# 3ch_mix_1_2.net
KiCad netlist of a schematic drawn in EAGLE
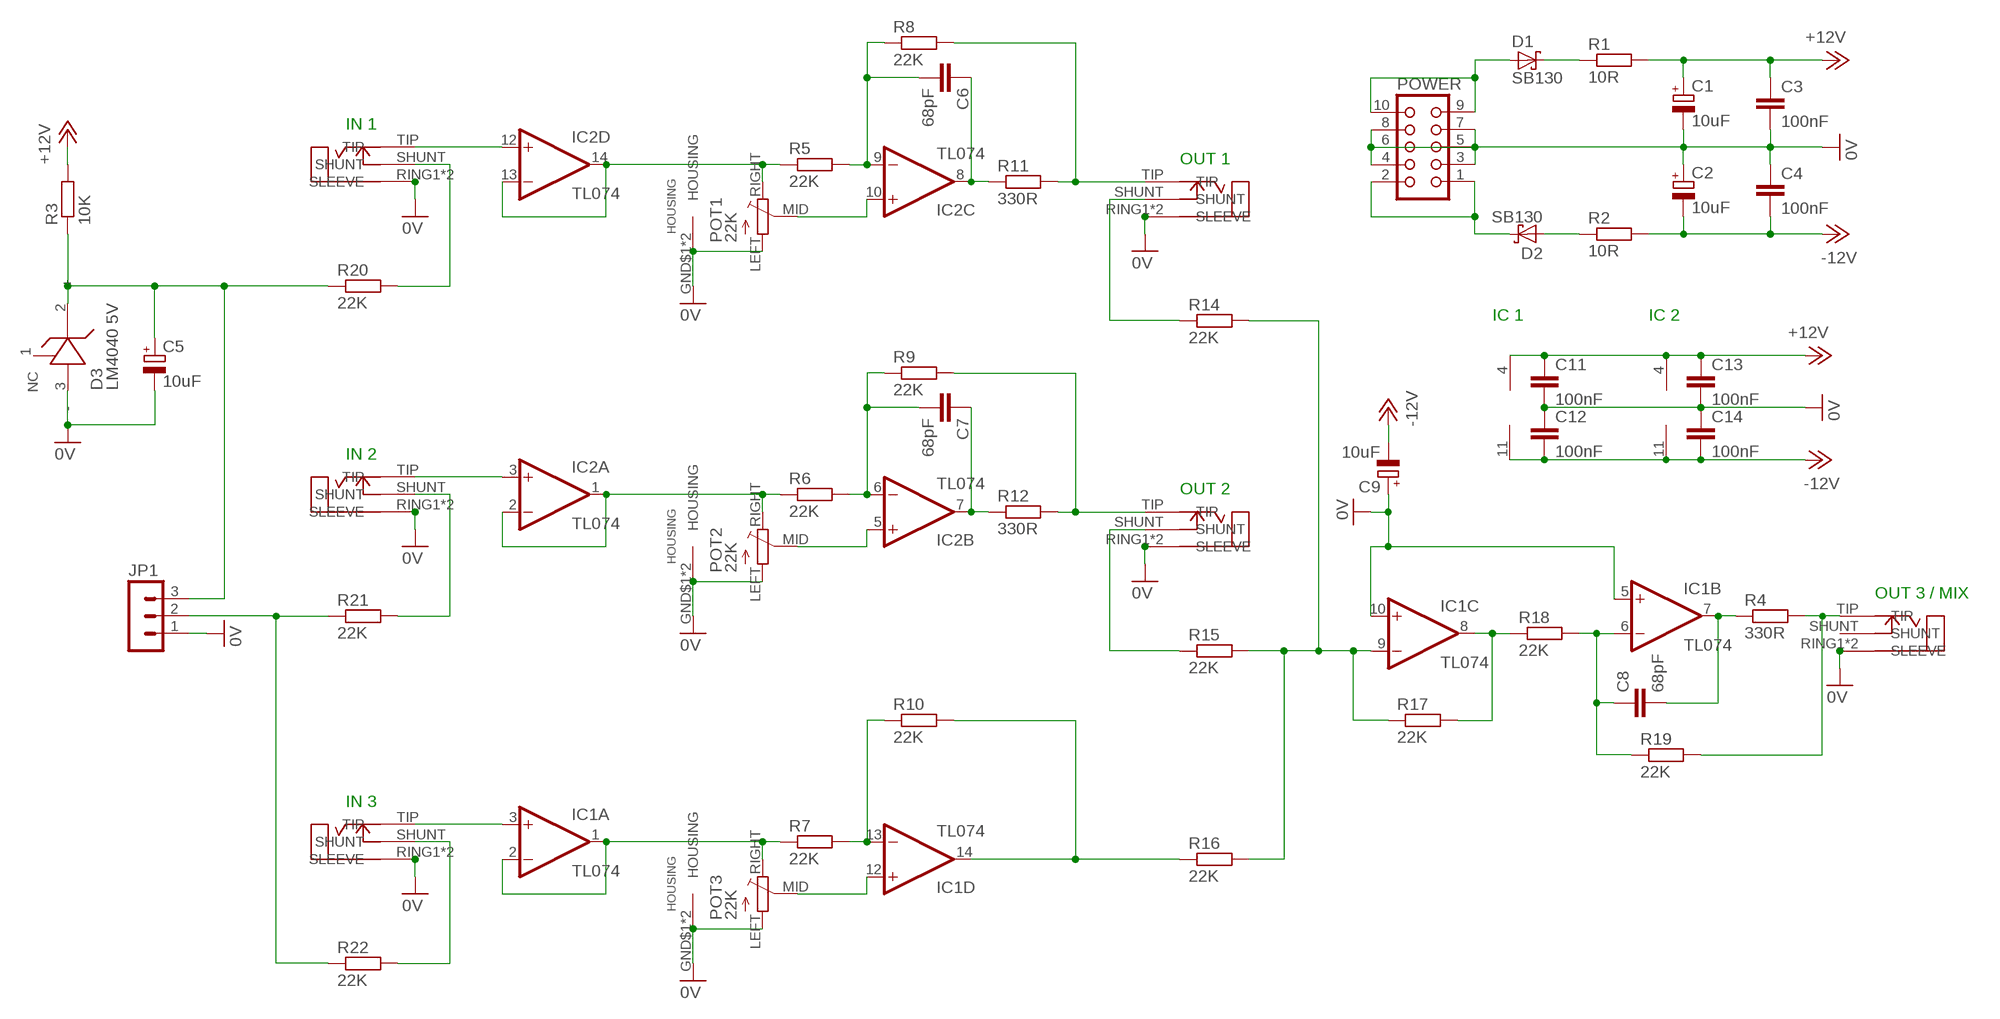
[diagram p0: schematic, sheet 1]

(export (version "E")
  (design (tool "Eeschema 10.0.6"))
  (components
    (comp (ref "C1")
      (value "10uF")
      (footprint "eagle-import:E2-5")
      (libsource (lib "eagle-import") (part "CPOL-EUE2-5"))
    )
    (comp (ref "C2")
      (value "10uF")
      (footprint "eagle-import:E2-5")
      (libsource (lib "eagle-import") (part "CPOL-EUE2-5"))
    )
    (comp (ref "C3")
      (value "100nF")
      (footprint "eagle-import:C025-024X044")
      (libsource (lib "eagle-import") (part "C-EU025-024X044"))
    )
    (comp (ref "C4")
      (value "100nF")
      (footprint "eagle-import:C025-024X044")
      (libsource (lib "eagle-import") (part "C-EU025-024X044"))
    )
    (comp (ref "C5")
      (value "10uF")
      (footprint "eagle-import:E2-5")
      (libsource (lib "eagle-import") (part "CPOL-EUE2-5"))
    )
    (comp (ref "C6")
      (value "68pF")
      (footprint "eagle-import:C025-024X044")
      (libsource (lib "eagle-import") (part "C-EU025-024X044"))
    )
    (comp (ref "C7")
      (value "68pF")
      (footprint "eagle-import:C025-024X044")
      (libsource (lib "eagle-import") (part "C-EU025-024X044"))
    )
    (comp (ref "C8")
      (value "68pF")
      (footprint "eagle-import:C025-024X044")
      (libsource (lib "eagle-import") (part "C-EU025-024X044"))
    )
    (comp (ref "C9")
      (value "10uF")
      (footprint "eagle-import:E2-5")
      (libsource (lib "eagle-import") (part "CPOL-EUE2-5"))
    )
    (comp (ref "C11")
      (value "100nF")
      (footprint "eagle-import:C025-024X044")
      (libsource (lib "eagle-import") (part "C-EU025-024X044"))
    )
    (comp (ref "C12")
      (value "100nF")
      (footprint "eagle-import:C025-024X044")
      (libsource (lib "eagle-import") (part "C-EU025-024X044"))
    )
    (comp (ref "C13")
      (value "100nF")
      (footprint "eagle-import:C025-024X044")
      (libsource (lib "eagle-import") (part "C-EU025-024X044"))
    )
    (comp (ref "C14")
      (value "100nF")
      (footprint "eagle-import:C025-024X044")
      (libsource (lib "eagle-import") (part "C-EU025-024X044"))
    )
    (comp (ref "D1")
      (value "SB130")
      (footprint "eagle-import:DO41-7")
      (libsource (lib "eagle-import") (part "SB130DO-204AL"))
    )
    (comp (ref "D2")
      (value "SB130")
      (footprint "eagle-import:DO41-7")
      (libsource (lib "eagle-import") (part "SB130DO-204AL"))
    )
    (comp (ref "D3")
      (value "LM4040 5V")
      (footprint "eagle-import:TO92-LINE")
      (libsource (lib "eagle-import") (part "LM4040"))
    )
    (comp (ref "IC1")
      (value "TL074")
      (footprint "eagle-import:DIL14")
      (libsource (lib "eagle-import") (part "TL074P"))
    )
    (comp (ref "IC2")
      (value "TL074")
      (footprint "eagle-import:DIL14")
      (libsource (lib "eagle-import") (part "TL074P"))
    )
    (comp (ref "IN1")
      (value "ERTHENVAR_3.5MM_JACK")
      (footprint "eagle-import:ERTHENVAR")
      (libsource (lib "eagle-import") (part "ERTHENVAR_3.5MM_JACK"))
    )
    (comp (ref "IN2")
      (value "ERTHENVAR_3.5MM_JACK")
      (footprint "eagle-import:ERTHENVAR")
      (libsource (lib "eagle-import") (part "ERTHENVAR_3.5MM_JACK"))
    )
    (comp (ref "IN3")
      (value "ERTHENVAR_3.5MM_JACK")
      (footprint "eagle-import:ERTHENVAR")
      (libsource (lib "eagle-import") (part "ERTHENVAR_3.5MM_JACK"))
    )
    (comp (ref "JP1")
      (value "MA03-1")
      (footprint "eagle-import:MA03-1")
      (libsource (lib "eagle-import") (part "MA03-1"))
    )
    (comp (ref "OUT1")
      (value "ERTHENVAR_3.5MM_JACK")
      (footprint "eagle-import:ERTHENVAR")
      (libsource (lib "eagle-import") (part "ERTHENVAR_3.5MM_JACK"))
    )
    (comp (ref "OUT2")
      (value "ERTHENVAR_3.5MM_JACK")
      (footprint "eagle-import:ERTHENVAR")
      (libsource (lib "eagle-import") (part "ERTHENVAR_3.5MM_JACK"))
    )
    (comp (ref "OUT3")
      (value "ERTHENVAR_3.5MM_JACK")
      (footprint "eagle-import:ERTHENVAR")
      (libsource (lib "eagle-import") (part "ERTHENVAR_3.5MM_JACK"))
    )
    (comp (ref "POT1")
      (value "22K")
      (footprint "eagle-import:POT-ALPHA9")
      (libsource (lib "eagle-import") (part "POT-ALPHA9"))
    )
    (comp (ref "POT2")
      (value "22K")
      (footprint "eagle-import:POT-ALPHA9")
      (libsource (lib "eagle-import") (part "POT-ALPHA9"))
    )
    (comp (ref "POT3")
      (value "22K")
      (footprint "eagle-import:POT-ALPHA9")
      (libsource (lib "eagle-import") (part "POT-ALPHA9"))
    )
    (comp (ref "POWER")
      (value "CON10L")
      (footprint "eagle-import:CON10L")
      (libsource (lib "eagle-import") (part "CON10L"))
    )
    (comp (ref "R1")
      (value "10R")
      (footprint "eagle-import:0207_9")
      (libsource (lib "eagle-import") (part "R-EU_0207/10"))
    )
    (comp (ref "R2")
      (value "10R")
      (footprint "eagle-import:0207_9")
      (libsource (lib "eagle-import") (part "R-EU_0207/10"))
    )
    (comp (ref "R3")
      (value "10K")
      (footprint "eagle-import:0204_5")
      (libsource (lib "eagle-import") (part "R-EU_0204/5"))
    )
    (comp (ref "R4")
      (value "330R")
      (footprint "eagle-import:0204_5")
      (libsource (lib "eagle-import") (part "R-EU_0204/5"))
    )
    (comp (ref "R5")
      (value "22K")
      (footprint "eagle-import:0204_5")
      (libsource (lib "eagle-import") (part "R-EU_0204/5"))
    )
    (comp (ref "R6")
      (value "22K")
      (footprint "eagle-import:0204_5")
      (libsource (lib "eagle-import") (part "R-EU_0204/5"))
    )
    (comp (ref "R7")
      (value "22K")
      (footprint "eagle-import:0204_5")
      (libsource (lib "eagle-import") (part "R-EU_0204/5"))
    )
    (comp (ref "R8")
      (value "22K")
      (footprint "eagle-import:0204_5")
      (libsource (lib "eagle-import") (part "R-EU_0204/5"))
    )
    (comp (ref "R9")
      (value "22K")
      (footprint "eagle-import:0204_5")
      (libsource (lib "eagle-import") (part "R-EU_0204/5"))
    )
    (comp (ref "R10")
      (value "22K")
      (footprint "eagle-import:0204_5")
      (libsource (lib "eagle-import") (part "R-EU_0204/5"))
    )
    (comp (ref "R11")
      (value "330R")
      (footprint "eagle-import:0204_5")
      (libsource (lib "eagle-import") (part "R-EU_0204/5"))
    )
    (comp (ref "R12")
      (value "330R")
      (footprint "eagle-import:0204_5")
      (libsource (lib "eagle-import") (part "R-EU_0204/5"))
    )
    (comp (ref "R14")
      (value "22K")
      (footprint "eagle-import:0204_5")
      (libsource (lib "eagle-import") (part "R-EU_0204/5"))
    )
    (comp (ref "R15")
      (value "22K")
      (footprint "eagle-import:0204_5")
      (libsource (lib "eagle-import") (part "R-EU_0204/5"))
    )
    (comp (ref "R16")
      (value "22K")
      (footprint "eagle-import:0204_5")
      (libsource (lib "eagle-import") (part "R-EU_0204/5"))
    )
    (comp (ref "R17")
      (value "22K")
      (footprint "eagle-import:0204_5")
      (libsource (lib "eagle-import") (part "R-EU_0204/5"))
    )
    (comp (ref "R18")
      (value "22K")
      (footprint "eagle-import:0204_5")
      (libsource (lib "eagle-import") (part "R-EU_0204/5"))
    )
    (comp (ref "R19")
      (value "22K")
      (footprint "eagle-import:0204_5")
      (libsource (lib "eagle-import") (part "R-EU_0204/5"))
    )
    (comp (ref "R20")
      (value "22K")
      (footprint "eagle-import:0204_5")
      (libsource (lib "eagle-import") (part "R-EU_0204/5"))
    )
    (comp (ref "R21")
      (value "22K")
      (footprint "eagle-import:0204_5")
      (libsource (lib "eagle-import") (part "R-EU_0204/5"))
    )
    (comp (ref "R22")
      (value "22K")
      (footprint "eagle-import:0204_5")
      (libsource (lib "eagle-import") (part "R-EU_0204/5"))
    )
  )
  (nets
    (net (code "1") (name "+12V") (class "Default")
      (node (ref "C1") (pin "+") (pinfunction "+_+") (pintype "passive"))
      (node (ref "C11") (pin "1") (pinfunction "1_1") (pintype "passive"))
      (node (ref "C13") (pin "1") (pinfunction "1_1") (pintype "passive"))
      (node (ref "C3") (pin "1") (pinfunction "1_1") (pintype "passive"))
      (node (ref "IC1") (pin "4") (pinfunction "V+_4") (pintype "power_in"))
      (node (ref "IC2") (pin "4") (pinfunction "V+_4") (pintype "power_in"))
      (node (ref "R1") (pin "2") (pinfunction "2_2") (pintype "passive"))
      (node (ref "R3") (pin "2") (pinfunction "2_2") (pintype "passive"))
    )
    (net (code "2") (name "-12V") (class "Default")
      (node (ref "C12") (pin "2") (pinfunction "2_2") (pintype "passive"))
      (node (ref "C14") (pin "2") (pinfunction "2_2") (pintype "passive"))
      (node (ref "C2") (pin "-") (pinfunction "-_-") (pintype "passive"))
      (node (ref "C4") (pin "2") (pinfunction "2_2") (pintype "passive"))
      (node (ref "C9") (pin "-") (pinfunction "-_-") (pintype "passive"))
      (node (ref "IC1") (pin "11") (pinfunction "V-_11") (pintype "power_in"))
      (node (ref "IC2") (pin "11") (pinfunction "V-_11") (pintype "power_in"))
      (node (ref "R2") (pin "2") (pinfunction "2_2") (pintype "passive"))
    )
    (net (code "3") (name "0V") (class "Default")
      (node (ref "C1") (pin "-") (pinfunction "-_-") (pintype "passive"))
      (node (ref "C11") (pin "2") (pinfunction "2_2") (pintype "passive"))
      (node (ref "C12") (pin "1") (pinfunction "1_1") (pintype "passive"))
      (node (ref "C13") (pin "2") (pinfunction "2_2") (pintype "passive"))
      (node (ref "C14") (pin "1") (pinfunction "1_1") (pintype "passive"))
      (node (ref "C2") (pin "+") (pinfunction "+_+") (pintype "passive"))
      (node (ref "C3") (pin "2") (pinfunction "2_2") (pintype "passive"))
      (node (ref "C4") (pin "1") (pinfunction "1_1") (pintype "passive"))
      (node (ref "C5") (pin "-") (pinfunction "-_-") (pintype "passive"))
      (node (ref "C9") (pin "+") (pinfunction "+_+") (pintype "passive"))
      (node (ref "D3") (pin "3") (pinfunction "-_3") (pintype "bidirectional"))
      (node (ref "IC1") (pin "10") (pinfunction "+IN_10") (pintype "input"))
      (node (ref "IC1") (pin "5") (pinfunction "+IN_5") (pintype "input"))
      (node (ref "IN1") (pin "RING1") (pinfunction "SLEEVE_RING1") (pintype "bidirectional"))
      (node (ref "IN1") (pin "RING2") (pinfunction "SLEEVE_RING2") (pintype "bidirectional"))
      (node (ref "IN2") (pin "RING1") (pinfunction "SLEEVE_RING1") (pintype "bidirectional"))
      (node (ref "IN2") (pin "RING2") (pinfunction "SLEEVE_RING2") (pintype "bidirectional"))
      (node (ref "IN3") (pin "RING1") (pinfunction "SLEEVE_RING1") (pintype "bidirectional"))
      (node (ref "IN3") (pin "RING2") (pinfunction "SLEEVE_RING2") (pintype "bidirectional"))
      (node (ref "JP1") (pin "1") (pinfunction "1_1") (pintype "passive"))
      (node (ref "OUT1") (pin "RING1") (pinfunction "SLEEVE_RING1") (pintype "bidirectional"))
      (node (ref "OUT1") (pin "RING2") (pinfunction "SLEEVE_RING2") (pintype "bidirectional"))
      (node (ref "OUT2") (pin "RING1") (pinfunction "SLEEVE_RING1") (pintype "bidirectional"))
      (node (ref "OUT2") (pin "RING2") (pinfunction "SLEEVE_RING2") (pintype "bidirectional"))
      (node (ref "OUT3") (pin "RING1") (pinfunction "SLEEVE_RING1") (pintype "bidirectional"))
      (node (ref "OUT3") (pin "RING2") (pinfunction "SLEEVE_RING2") (pintype "bidirectional"))
      (node (ref "POT1") (pin "GND$1") (pinfunction "HOUSING_GND$1") (pintype "bidirectional"))
      (node (ref "POT1") (pin "GND$2") (pinfunction "HOUSING_GND$2") (pintype "bidirectional"))
      (node (ref "POT1") (pin "LEFT") (pinfunction "LEFT_LEFT") (pintype "passive"))
      (node (ref "POT2") (pin "GND$1") (pinfunction "HOUSING_GND$1") (pintype "bidirectional"))
      (node (ref "POT2") (pin "GND$2") (pinfunction "HOUSING_GND$2") (pintype "bidirectional"))
      (node (ref "POT2") (pin "LEFT") (pinfunction "LEFT_LEFT") (pintype "passive"))
      (node (ref "POT3") (pin "GND$1") (pinfunction "HOUSING_GND$1") (pintype "bidirectional"))
      (node (ref "POT3") (pin "GND$2") (pinfunction "HOUSING_GND$2") (pintype "bidirectional"))
      (node (ref "POT3") (pin "LEFT") (pinfunction "LEFT_LEFT") (pintype "passive"))
      (node (ref "POWER") (pin "3") (pinfunction "3_3") (pintype "passive"))
      (node (ref "POWER") (pin "4") (pinfunction "4_4") (pintype "passive"))
      (node (ref "POWER") (pin "5") (pinfunction "5_5") (pintype "passive"))
      (node (ref "POWER") (pin "6") (pinfunction "6_6") (pintype "passive"))
      (node (ref "POWER") (pin "7") (pinfunction "7_7") (pintype "passive"))
      (node (ref "POWER") (pin "8") (pinfunction "8_8") (pintype "passive"))
    )
    (net (code "4") (name "Net-(D1-PadA)") (class "Default")
      (node (ref "D1") (pin "A") (pinfunction "A_A") (pintype "passive"))
      (node (ref "POWER") (pin "10") (pinfunction "10_10") (pintype "passive"))
      (node (ref "POWER") (pin "9") (pinfunction "9_9") (pintype "passive"))
    )
    (net (code "5") (name "Net-(D1-PadC)") (class "Default")
      (node (ref "D1") (pin "C") (pinfunction "C_C") (pintype "passive"))
      (node (ref "R1") (pin "1") (pinfunction "1_1") (pintype "passive"))
    )
    (net (code "6") (name "Net-(D2-PadA)") (class "Default")
      (node (ref "D2") (pin "A") (pinfunction "A_A") (pintype "passive"))
      (node (ref "R2") (pin "1") (pinfunction "1_1") (pintype "passive"))
    )
    (net (code "7") (name "Net-(D2-PadC)") (class "Default")
      (node (ref "D2") (pin "C") (pinfunction "C_C") (pintype "passive"))
      (node (ref "POWER") (pin "1") (pinfunction "1_1") (pintype "passive"))
      (node (ref "POWER") (pin "2") (pinfunction "2_2") (pintype "passive"))
    )
    (net (code "8") (name "Net-(D3-+)") (class "Default")
      (node (ref "C5") (pin "+") (pinfunction "+_+") (pintype "passive"))
      (node (ref "D3") (pin "2") (pinfunction "+_2") (pintype "bidirectional"))
      (node (ref "JP1") (pin "3") (pinfunction "3_3") (pintype "passive"))
      (node (ref "R20") (pin "1") (pinfunction "1_1") (pintype "passive"))
      (node (ref "R3") (pin "1") (pinfunction "1_1") (pintype "passive"))
    )
    (net (code "9") (name "Net-(IC1A-+IN)") (class "Default")
      (node (ref "IC1") (pin "3") (pinfunction "+IN_3") (pintype "input"))
      (node (ref "IN3") (pin "TIP") (pinfunction "TIP_TIP") (pintype "bidirectional"))
    )
    (net (code "10") (name "Net-(IC1A--IN)") (class "Default")
      (node (ref "IC1") (pin "1") (pinfunction "OUT_1") (pintype "output"))
      (node (ref "IC1") (pin "2") (pinfunction "-IN_2") (pintype "input"))
      (node (ref "POT3") (pin "RIGHT") (pinfunction "RIGHT_RIGHT") (pintype "passive"))
      (node (ref "R7") (pin "1") (pinfunction "1_1") (pintype "passive"))
    )
    (net (code "11") (name "Net-(IC1B--IN)") (class "Default")
      (node (ref "C8") (pin "1") (pinfunction "1_1") (pintype "passive"))
      (node (ref "IC1") (pin "6") (pinfunction "-IN_6") (pintype "input"))
      (node (ref "R18") (pin "2") (pinfunction "2_2") (pintype "passive"))
      (node (ref "R19") (pin "1") (pinfunction "1_1") (pintype "passive"))
    )
    (net (code "12") (name "Net-(IC1B-OUT)") (class "Default")
      (node (ref "C8") (pin "2") (pinfunction "2_2") (pintype "passive"))
      (node (ref "IC1") (pin "7") (pinfunction "OUT_7") (pintype "output"))
      (node (ref "R4") (pin "1") (pinfunction "1_1") (pintype "passive"))
    )
    (net (code "13") (name "Net-(IC1C--IN)") (class "Default")
      (node (ref "IC1") (pin "9") (pinfunction "-IN_9") (pintype "input"))
      (node (ref "R14") (pin "2") (pinfunction "2_2") (pintype "passive"))
      (node (ref "R15") (pin "2") (pinfunction "2_2") (pintype "passive"))
      (node (ref "R16") (pin "2") (pinfunction "2_2") (pintype "passive"))
      (node (ref "R17") (pin "1") (pinfunction "1_1") (pintype "passive"))
    )
    (net (code "14") (name "Net-(IC1C-OUT)") (class "Default")
      (node (ref "IC1") (pin "8") (pinfunction "OUT_8") (pintype "output"))
      (node (ref "R17") (pin "2") (pinfunction "2_2") (pintype "passive"))
      (node (ref "R18") (pin "1") (pinfunction "1_1") (pintype "passive"))
    )
    (net (code "15") (name "Net-(IC1D-+IN)") (class "Default")
      (node (ref "IC1") (pin "12") (pinfunction "+IN_12") (pintype "input"))
      (node (ref "POT3") (pin "MID") (pinfunction "MID_MID") (pintype "passive"))
    )
    (net (code "16") (name "Net-(IC1D--IN)") (class "Default")
      (node (ref "IC1") (pin "13") (pinfunction "-IN_13") (pintype "input"))
      (node (ref "R10") (pin "1") (pinfunction "1_1") (pintype "passive"))
      (node (ref "R7") (pin "2") (pinfunction "2_2") (pintype "passive"))
    )
    (net (code "17") (name "Net-(IC1D-OUT)") (class "Default")
      (node (ref "IC1") (pin "14") (pinfunction "OUT_14") (pintype "output"))
      (node (ref "R10") (pin "2") (pinfunction "2_2") (pintype "passive"))
      (node (ref "R16") (pin "1") (pinfunction "1_1") (pintype "passive"))
    )
    (net (code "18") (name "Net-(IC2A-+IN)") (class "Default")
      (node (ref "IC2") (pin "3") (pinfunction "+IN_3") (pintype "input"))
      (node (ref "IN2") (pin "TIP") (pinfunction "TIP_TIP") (pintype "bidirectional"))
    )
    (net (code "19") (name "Net-(IC2A--IN)") (class "Default")
      (node (ref "IC2") (pin "1") (pinfunction "OUT_1") (pintype "output"))
      (node (ref "IC2") (pin "2") (pinfunction "-IN_2") (pintype "input"))
      (node (ref "POT2") (pin "RIGHT") (pinfunction "RIGHT_RIGHT") (pintype "passive"))
      (node (ref "R6") (pin "1") (pinfunction "1_1") (pintype "passive"))
    )
    (net (code "20") (name "Net-(IC2B-+IN)") (class "Default")
      (node (ref "IC2") (pin "5") (pinfunction "+IN_5") (pintype "input"))
      (node (ref "POT2") (pin "MID") (pinfunction "MID_MID") (pintype "passive"))
    )
    (net (code "21") (name "Net-(IC2B--IN)") (class "Default")
      (node (ref "C7") (pin "2") (pinfunction "2_2") (pintype "passive"))
      (node (ref "IC2") (pin "6") (pinfunction "-IN_6") (pintype "input"))
      (node (ref "R6") (pin "2") (pinfunction "2_2") (pintype "passive"))
      (node (ref "R9") (pin "1") (pinfunction "1_1") (pintype "passive"))
    )
    (net (code "22") (name "Net-(IC2B-OUT)") (class "Default")
      (node (ref "C7") (pin "1") (pinfunction "1_1") (pintype "passive"))
      (node (ref "IC2") (pin "7") (pinfunction "OUT_7") (pintype "output"))
      (node (ref "R12") (pin "1") (pinfunction "1_1") (pintype "passive"))
    )
    (net (code "23") (name "Net-(IC2C-+IN)") (class "Default")
      (node (ref "IC2") (pin "10") (pinfunction "+IN_10") (pintype "input"))
      (node (ref "POT1") (pin "MID") (pinfunction "MID_MID") (pintype "passive"))
    )
    (net (code "24") (name "Net-(IC2C--IN)") (class "Default")
      (node (ref "C6") (pin "2") (pinfunction "2_2") (pintype "passive"))
      (node (ref "IC2") (pin "9") (pinfunction "-IN_9") (pintype "input"))
      (node (ref "R5") (pin "2") (pinfunction "2_2") (pintype "passive"))
      (node (ref "R8") (pin "1") (pinfunction "1_1") (pintype "passive"))
    )
    (net (code "25") (name "Net-(IC2C-OUT)") (class "Default")
      (node (ref "C6") (pin "1") (pinfunction "1_1") (pintype "passive"))
      (node (ref "IC2") (pin "8") (pinfunction "OUT_8") (pintype "output"))
      (node (ref "R11") (pin "1") (pinfunction "1_1") (pintype "passive"))
    )
    (net (code "26") (name "Net-(IC2D-+IN)") (class "Default")
      (node (ref "IC2") (pin "12") (pinfunction "+IN_12") (pintype "input"))
      (node (ref "IN1") (pin "TIP") (pinfunction "TIP_TIP") (pintype "bidirectional"))
    )
    (net (code "27") (name "Net-(IC2D--IN)") (class "Default")
      (node (ref "IC2") (pin "13") (pinfunction "-IN_13") (pintype "input"))
      (node (ref "IC2") (pin "14") (pinfunction "OUT_14") (pintype "output"))
      (node (ref "POT1") (pin "RIGHT") (pinfunction "RIGHT_RIGHT") (pintype "passive"))
      (node (ref "R5") (pin "1") (pinfunction "1_1") (pintype "passive"))
    )
    (net (code "28") (name "Net-(IN1-PadSHUNT)") (class "Default")
      (node (ref "IN1") (pin "SHUNT") (pinfunction "SHUNT_SHUNT") (pintype "bidirectional"))
      (node (ref "R20") (pin "2") (pinfunction "2_2") (pintype "passive"))
    )
    (net (code "29") (name "Net-(IN2-PadSHUNT)") (class "Default")
      (node (ref "IN2") (pin "SHUNT") (pinfunction "SHUNT_SHUNT") (pintype "bidirectional"))
      (node (ref "R21") (pin "2") (pinfunction "2_2") (pintype "passive"))
    )
    (net (code "30") (name "Net-(IN3-PadSHUNT)") (class "Default")
      (node (ref "IN3") (pin "SHUNT") (pinfunction "SHUNT_SHUNT") (pintype "bidirectional"))
      (node (ref "R22") (pin "2") (pinfunction "2_2") (pintype "passive"))
    )
    (net (code "31") (name "Net-(JP1-Pad2)") (class "Default")
      (node (ref "JP1") (pin "2") (pinfunction "2_2") (pintype "passive"))
      (node (ref "R21") (pin "1") (pinfunction "1_1") (pintype "passive"))
      (node (ref "R22") (pin "1") (pinfunction "1_1") (pintype "passive"))
    )
    (net (code "32") (name "Net-(OUT1-PadSHUNT)") (class "Default")
      (node (ref "OUT1") (pin "SHUNT") (pinfunction "SHUNT_SHUNT") (pintype "bidirectional"))
      (node (ref "R14") (pin "1") (pinfunction "1_1") (pintype "passive"))
    )
    (net (code "33") (name "Net-(OUT1-PadTIP)") (class "Default")
      (node (ref "OUT1") (pin "TIP") (pinfunction "TIP_TIP") (pintype "bidirectional"))
      (node (ref "R11") (pin "2") (pinfunction "2_2") (pintype "passive"))
      (node (ref "R8") (pin "2") (pinfunction "2_2") (pintype "passive"))
    )
    (net (code "34") (name "Net-(OUT2-PadSHUNT)") (class "Default")
      (node (ref "OUT2") (pin "SHUNT") (pinfunction "SHUNT_SHUNT") (pintype "bidirectional"))
      (node (ref "R15") (pin "1") (pinfunction "1_1") (pintype "passive"))
    )
    (net (code "35") (name "Net-(OUT2-PadTIP)") (class "Default")
      (node (ref "OUT2") (pin "TIP") (pinfunction "TIP_TIP") (pintype "bidirectional"))
      (node (ref "R12") (pin "2") (pinfunction "2_2") (pintype "passive"))
      (node (ref "R9") (pin "2") (pinfunction "2_2") (pintype "passive"))
    )
    (net (code "36") (name "Net-(OUT3-PadTIP)") (class "Default")
      (node (ref "OUT3") (pin "TIP") (pinfunction "TIP_TIP") (pintype "bidirectional"))
      (node (ref "R19") (pin "2") (pinfunction "2_2") (pintype "passive"))
      (node (ref "R4") (pin "2") (pinfunction "2_2") (pintype "passive"))
    )
    (net (code "37") (name "unconnected-(D3-NC-Pad1)") (class "Default")
      (node (ref "D3") (pin "1") (pinfunction "NC_1") (pintype "no_connect"))
    )
    (net (code "38") (name "unconnected-(OUT3-PadSHUNT)") (class "Default")
      (node (ref "OUT3") (pin "SHUNT") (pinfunction "SHUNT_SHUNT") (pintype "bidirectional"))
    )
  )
)
